# ncn8025-breakout.net
KiCad netlist of a schematic drawn in EAGLE
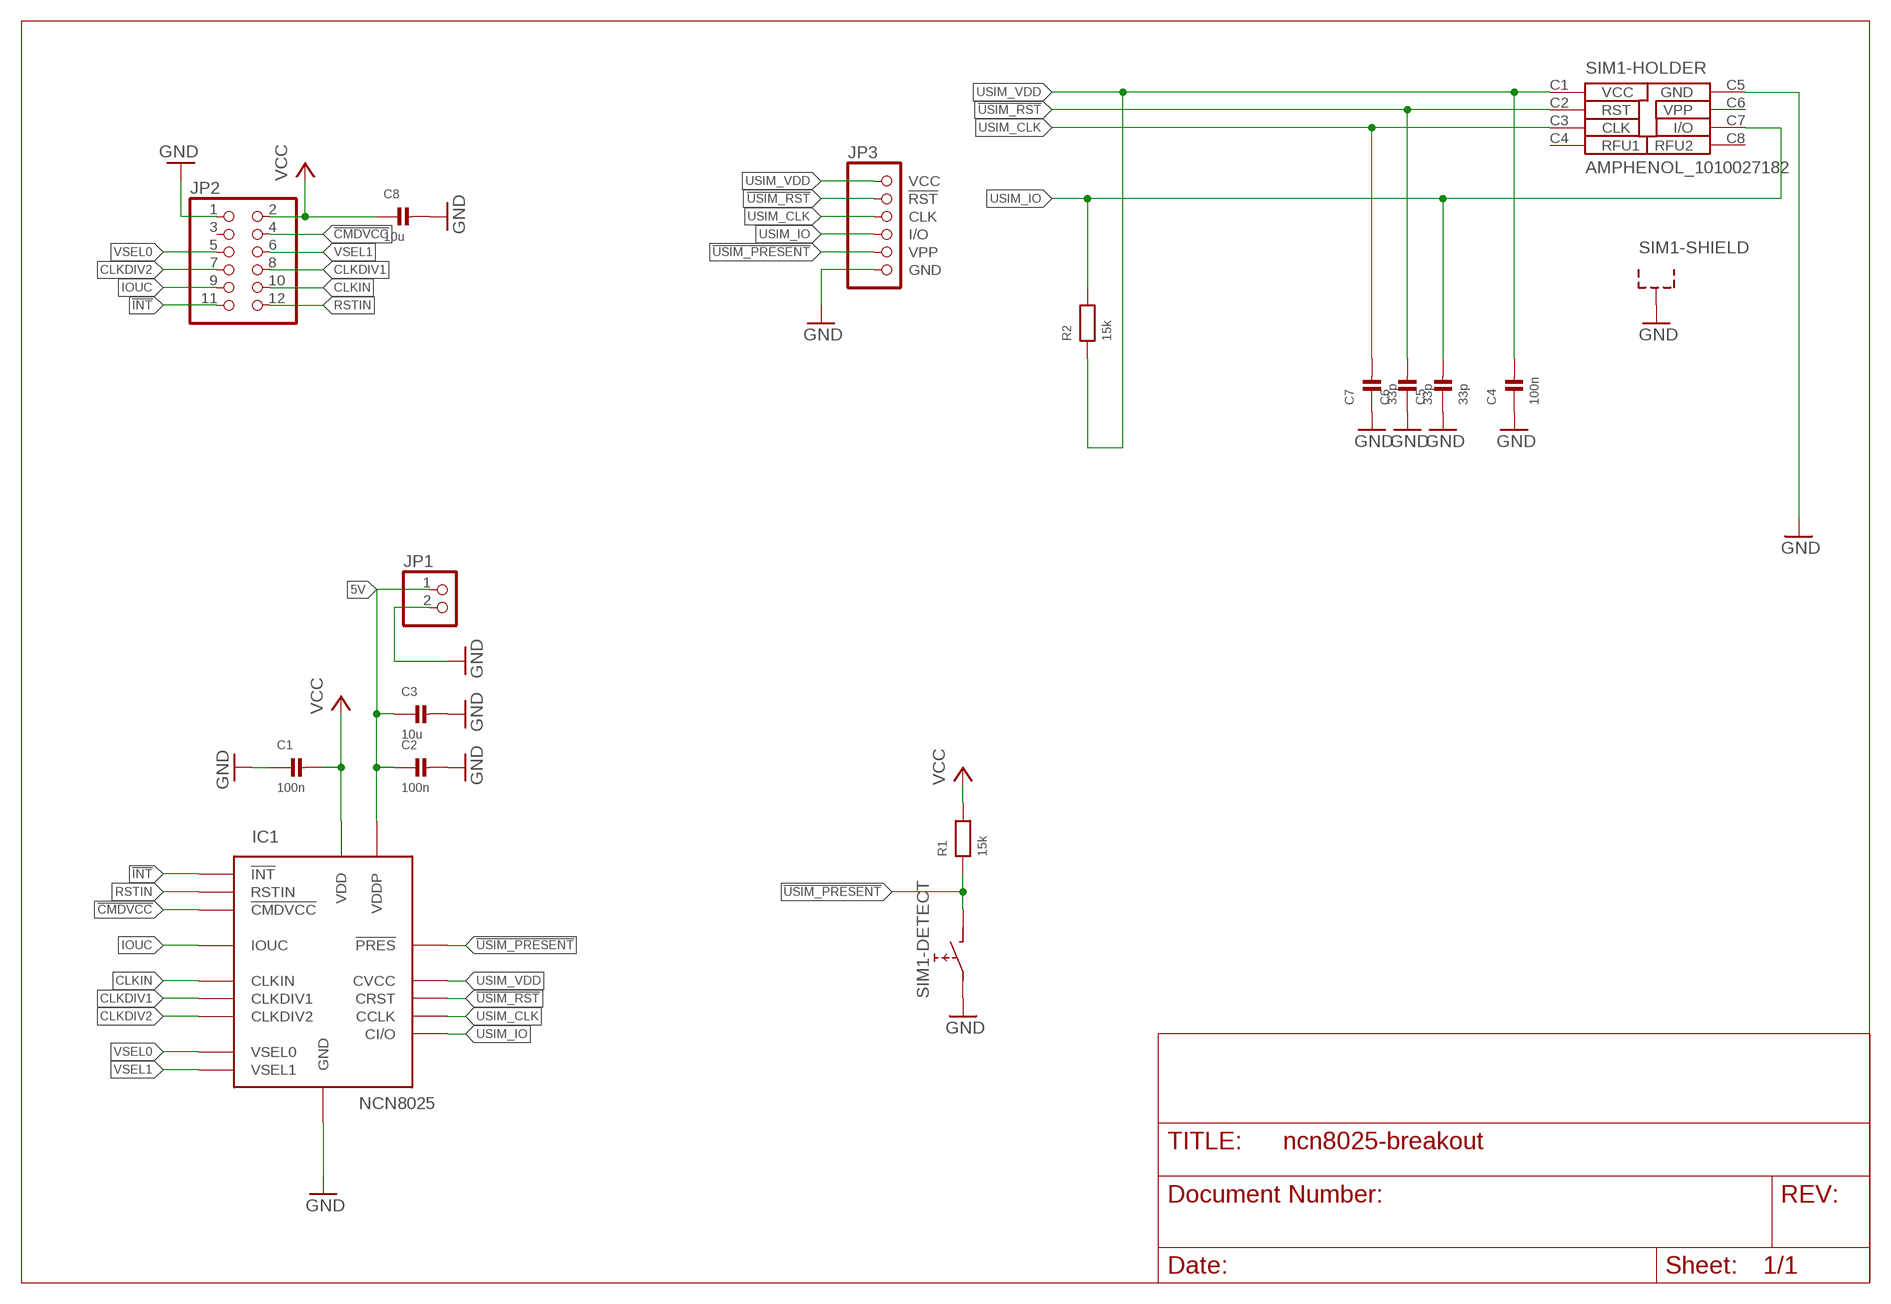
[diagram p0: schematic, sheet 1]

(export (version "E")
  (design (tool "Eeschema 10.0.6"))
  (components
    (comp (ref "C1")
      (value "100n")
      (footprint "eagle-import:_0603")
      (libsource (lib "eagle-import") (part "CAP_CERAMIC_0603"))
    )
    (comp (ref "C2")
      (value "100n")
      (footprint "eagle-import:_0603")
      (libsource (lib "eagle-import") (part "CAP_CERAMIC_0603"))
    )
    (comp (ref "C3")
      (value "10u")
      (footprint "eagle-import:_0603")
      (libsource (lib "eagle-import") (part "CAP_CERAMIC_0603"))
    )
    (comp (ref "C4")
      (value "100n")
      (footprint "eagle-import:_0603")
      (libsource (lib "eagle-import") (part "CAP_CERAMIC_0603"))
    )
    (comp (ref "C5")
      (value "33p")
      (footprint "eagle-import:_0603")
      (libsource (lib "eagle-import") (part "CAP_CERAMIC_0603"))
    )
    (comp (ref "C6")
      (value "33p")
      (footprint "eagle-import:_0603")
      (libsource (lib "eagle-import") (part "CAP_CERAMIC_0603"))
    )
    (comp (ref "C7")
      (value "33p")
      (footprint "eagle-import:_0603")
      (libsource (lib "eagle-import") (part "CAP_CERAMIC_0603"))
    )
    (comp (ref "C8")
      (value "10u")
      (footprint "eagle-import:_0603")
      (libsource (lib "eagle-import") (part "CAP_CERAMIC_0603"))
    )
    (comp (ref "IC1")
      (value "NCN8025")
      (footprint "eagle-import:QFN16_3X3")
      (libsource (lib "eagle-import") (part "NCN8025"))
    )
    (comp (ref "JP1")
      (value "PINHD-1X2")
      (footprint "eagle-import:1X02")
      (libsource (lib "eagle-import") (part "PINHD-1X2"))
    )
    (comp (ref "JP2")
      (value "PINHD-2X6")
      (footprint "eagle-import:2X06")
      (libsource (lib "eagle-import") (part "PINHD-2X6"))
    )
    (comp (ref "JP3")
      (value "PINHD-1X6")
      (footprint "eagle-import:1X06")
      (libsource (lib "eagle-import") (part "PINHD-1X6"))
    )
    (comp (ref "R1")
      (value "15k")
      (footprint "eagle-import:_0603")
      (libsource (lib "eagle-import") (part "RESISTOR_0603"))
    )
    (comp (ref "R2")
      (value "15k")
      (footprint "eagle-import:_0603")
      (libsource (lib "eagle-import") (part "RESISTOR_0603"))
    )
    (comp (ref "SIM1")
      (value "AMPHENOL_1010027182")
      (footprint "eagle-import:SIM-AMPHENOL")
      (libsource (lib "eagle-import") (part "AMPHENOL_1010027182"))
    )
  )
  (nets
    (net (code "1") (name "/VPP") (class "Default")
      (node (ref "SIM1") (pin "C6") (pinfunction "VPP_C6") (pintype "power_in"))
    )
    (net (code "2") (name "/~{CMDVCC}") (class "Default")
      (node (ref "IC1") (pin "8") (pinfunction "~{CMDVCC}_8") (pintype "input"))
      (node (ref "JP2") (pin "4") (pinfunction "4_4") (pintype "passive"))
    )
    (net (code "3") (name "/~{INT}") (class "Default")
      (node (ref "IC1") (pin "11") (pinfunction "~{INT}_11") (pintype "output"))
      (node (ref "JP2") (pin "11") (pinfunction "11_11") (pintype "passive"))
    )
    (net (code "4") (name "/~{USIM_PRESENT}") (class "Default")
      (node (ref "IC1") (pin "3") (pinfunction "~{PRES}_3") (pintype "input"))
      (node (ref "JP3") (pin "5") (pinfunction "VPP_5") (pintype "power_in"))
      (node (ref "R1") (pin "1") (pinfunction "1_1") (pintype "passive"))
      (node (ref "SIM1") (pin "SW2") (pinfunction "1_SW2") (pintype "passive"))
    )
    (net (code "5") (name "/~{USIM_RST}") (class "Default")
      (node (ref "C6") (pin "2") (pinfunction "2_2") (pintype "passive"))
      (node (ref "IC1") (pin "6") (pinfunction "CRST_6") (pintype "output"))
      (node (ref "JP3") (pin "2") (pinfunction "~{RST}_2") (pintype "output"))
      (node (ref "SIM1") (pin "C2") (pinfunction "RST_C2") (pintype "input"))
    )
    (net (code "6") (name "5V") (class "Default")
      (node (ref "C2") (pin "1") (pinfunction "1_1") (pintype "passive"))
      (node (ref "C3") (pin "1") (pinfunction "1_1") (pintype "passive"))
      (node (ref "IC1") (pin "2") (pinfunction "VDDP_2") (pintype "power_in"))
      (node (ref "JP1") (pin "1") (pinfunction "1_1") (pintype "passive"))
    )
    (net (code "7") (name "CLKDIV1") (class "Default")
      (node (ref "IC1") (pin "14") (pinfunction "CLKDIV1_14") (pintype "input"))
      (node (ref "JP2") (pin "8") (pinfunction "8_8") (pintype "passive"))
    )
    (net (code "8") (name "CLKDIV2") (class "Default")
      (node (ref "IC1") (pin "15") (pinfunction "CLKDIV2_15") (pintype "input"))
      (node (ref "JP2") (pin "7") (pinfunction "7_7") (pintype "passive"))
    )
    (net (code "9") (name "CLKIN") (class "Default")
      (node (ref "IC1") (pin "12") (pinfunction "CLKIN_12") (pintype "input"))
      (node (ref "JP2") (pin "10") (pinfunction "10_10") (pintype "passive"))
    )
    (net (code "10") (name "GND") (class "Default")
      (node (ref "C1") (pin "1") (pinfunction "1_1") (pintype "passive"))
      (node (ref "C2") (pin "2") (pinfunction "2_2") (pintype "passive"))
      (node (ref "C3") (pin "2") (pinfunction "2_2") (pintype "passive"))
      (node (ref "C4") (pin "1") (pinfunction "1_1") (pintype "passive"))
      (node (ref "C5") (pin "1") (pinfunction "1_1") (pintype "passive"))
      (node (ref "C6") (pin "1") (pinfunction "1_1") (pintype "passive"))
      (node (ref "C7") (pin "1") (pinfunction "1_1") (pintype "passive"))
      (node (ref "C8") (pin "2") (pinfunction "2_2") (pintype "passive"))
      (node (ref "IC1") (pin "EXPPAD") (pinfunction "GND_EXPPAD") (pintype "power_in"))
      (node (ref "JP1") (pin "2") (pinfunction "2_2") (pintype "passive"))
      (node (ref "JP2") (pin "1") (pinfunction "1_1") (pintype "passive"))
      (node (ref "JP3") (pin "6") (pinfunction "GND_6") (pintype "passive"))
      (node (ref "SIM1") (pin "@2") (pinfunction "SHLD_@2") (pintype "passive"))
      (node (ref "SIM1") (pin "@3") (pinfunction "SHLD_@3") (pintype "passive"))
      (node (ref "SIM1") (pin "C5") (pinfunction "GND_C5") (pintype "passive"))
      (node (ref "SIM1") (pin "SW1") (pinfunction "0_SW1") (pintype "passive"))
    )
    (net (code "11") (name "IOUC") (class "Default")
      (node (ref "IC1") (pin "13") (pinfunction "IOUC_13") (pintype "bidirectional"))
      (node (ref "JP2") (pin "9") (pinfunction "9_9") (pintype "passive"))
    )
    (net (code "12") (name "RSTIN") (class "Default")
      (node (ref "IC1") (pin "9") (pinfunction "RSTIN_9") (pintype "input"))
      (node (ref "JP2") (pin "12") (pinfunction "12_12") (pintype "passive"))
    )
    (net (code "13") (name "USIM_CLK") (class "Default")
      (node (ref "C7") (pin "2") (pinfunction "2_2") (pintype "passive"))
      (node (ref "IC1") (pin "5") (pinfunction "CCLK_5") (pintype "output"))
      (node (ref "JP3") (pin "3") (pinfunction "CLK_3") (pintype "output"))
      (node (ref "SIM1") (pin "C3") (pinfunction "CLK_C3") (pintype "input"))
    )
    (net (code "14") (name "USIM_IO") (class "Default")
      (node (ref "C5") (pin "2") (pinfunction "2_2") (pintype "passive"))
      (node (ref "IC1") (pin "4") (pinfunction "CI/O_4") (pintype "bidirectional"))
      (node (ref "JP3") (pin "4") (pinfunction "I/O_4") (pintype "bidirectional"))
      (node (ref "R2") (pin "2") (pinfunction "2_2") (pintype "passive"))
      (node (ref "SIM1") (pin "C7") (pinfunction "I/O_C7") (pintype "bidirectional"))
    )
    (net (code "15") (name "USIM_VDD") (class "Default")
      (node (ref "C4") (pin "2") (pinfunction "2_2") (pintype "passive"))
      (node (ref "IC1") (pin "7") (pinfunction "CVCC_7") (pintype "power_in"))
      (node (ref "JP3") (pin "1") (pinfunction "VCC_1") (pintype "power_in"))
      (node (ref "R2") (pin "1") (pinfunction "1_1") (pintype "passive"))
      (node (ref "SIM1") (pin "C1") (pinfunction "VCC_C1") (pintype "power_in"))
    )
    (net (code "16") (name "VCC") (class "Default")
      (node (ref "C1") (pin "2") (pinfunction "2_2") (pintype "passive"))
      (node (ref "C8") (pin "1") (pinfunction "1_1") (pintype "passive"))
      (node (ref "IC1") (pin "10") (pinfunction "VDD_10") (pintype "power_in"))
      (node (ref "JP2") (pin "2") (pinfunction "2_2") (pintype "passive"))
      (node (ref "R1") (pin "2") (pinfunction "2_2") (pintype "passive"))
    )
    (net (code "17") (name "VSEL0") (class "Default")
      (node (ref "IC1") (pin "1") (pinfunction "VSEL0_1") (pintype "input"))
      (node (ref "JP2") (pin "5") (pinfunction "5_5") (pintype "passive"))
    )
    (net (code "18") (name "VSEL1") (class "Default")
      (node (ref "IC1") (pin "16") (pinfunction "VSEL1_16") (pintype "input"))
      (node (ref "JP2") (pin "6") (pinfunction "6_6") (pintype "passive"))
    )
    (net (code "19") (name "unconnected-(JP2-Pad3)") (class "Default")
      (node (ref "JP2") (pin "3") (pinfunction "3_3") (pintype "passive"))
    )
    (net (code "20") (name "unconnected-(SIM1B-RFU1-PadC4)") (class "Default")
      (node (ref "SIM1") (pin "C4") (pinfunction "RFU1_C4") (pintype "no_connect"))
    )
    (net (code "21") (name "unconnected-(SIM1B-RFU2-PadC8)") (class "Default")
      (node (ref "SIM1") (pin "C8") (pinfunction "RFU2_C8") (pintype "no_connect"))
    )
  )
)
